# Rocekt_test_stand_input_2_0.net
KiCad netlist of a schematic drawn in EAGLE
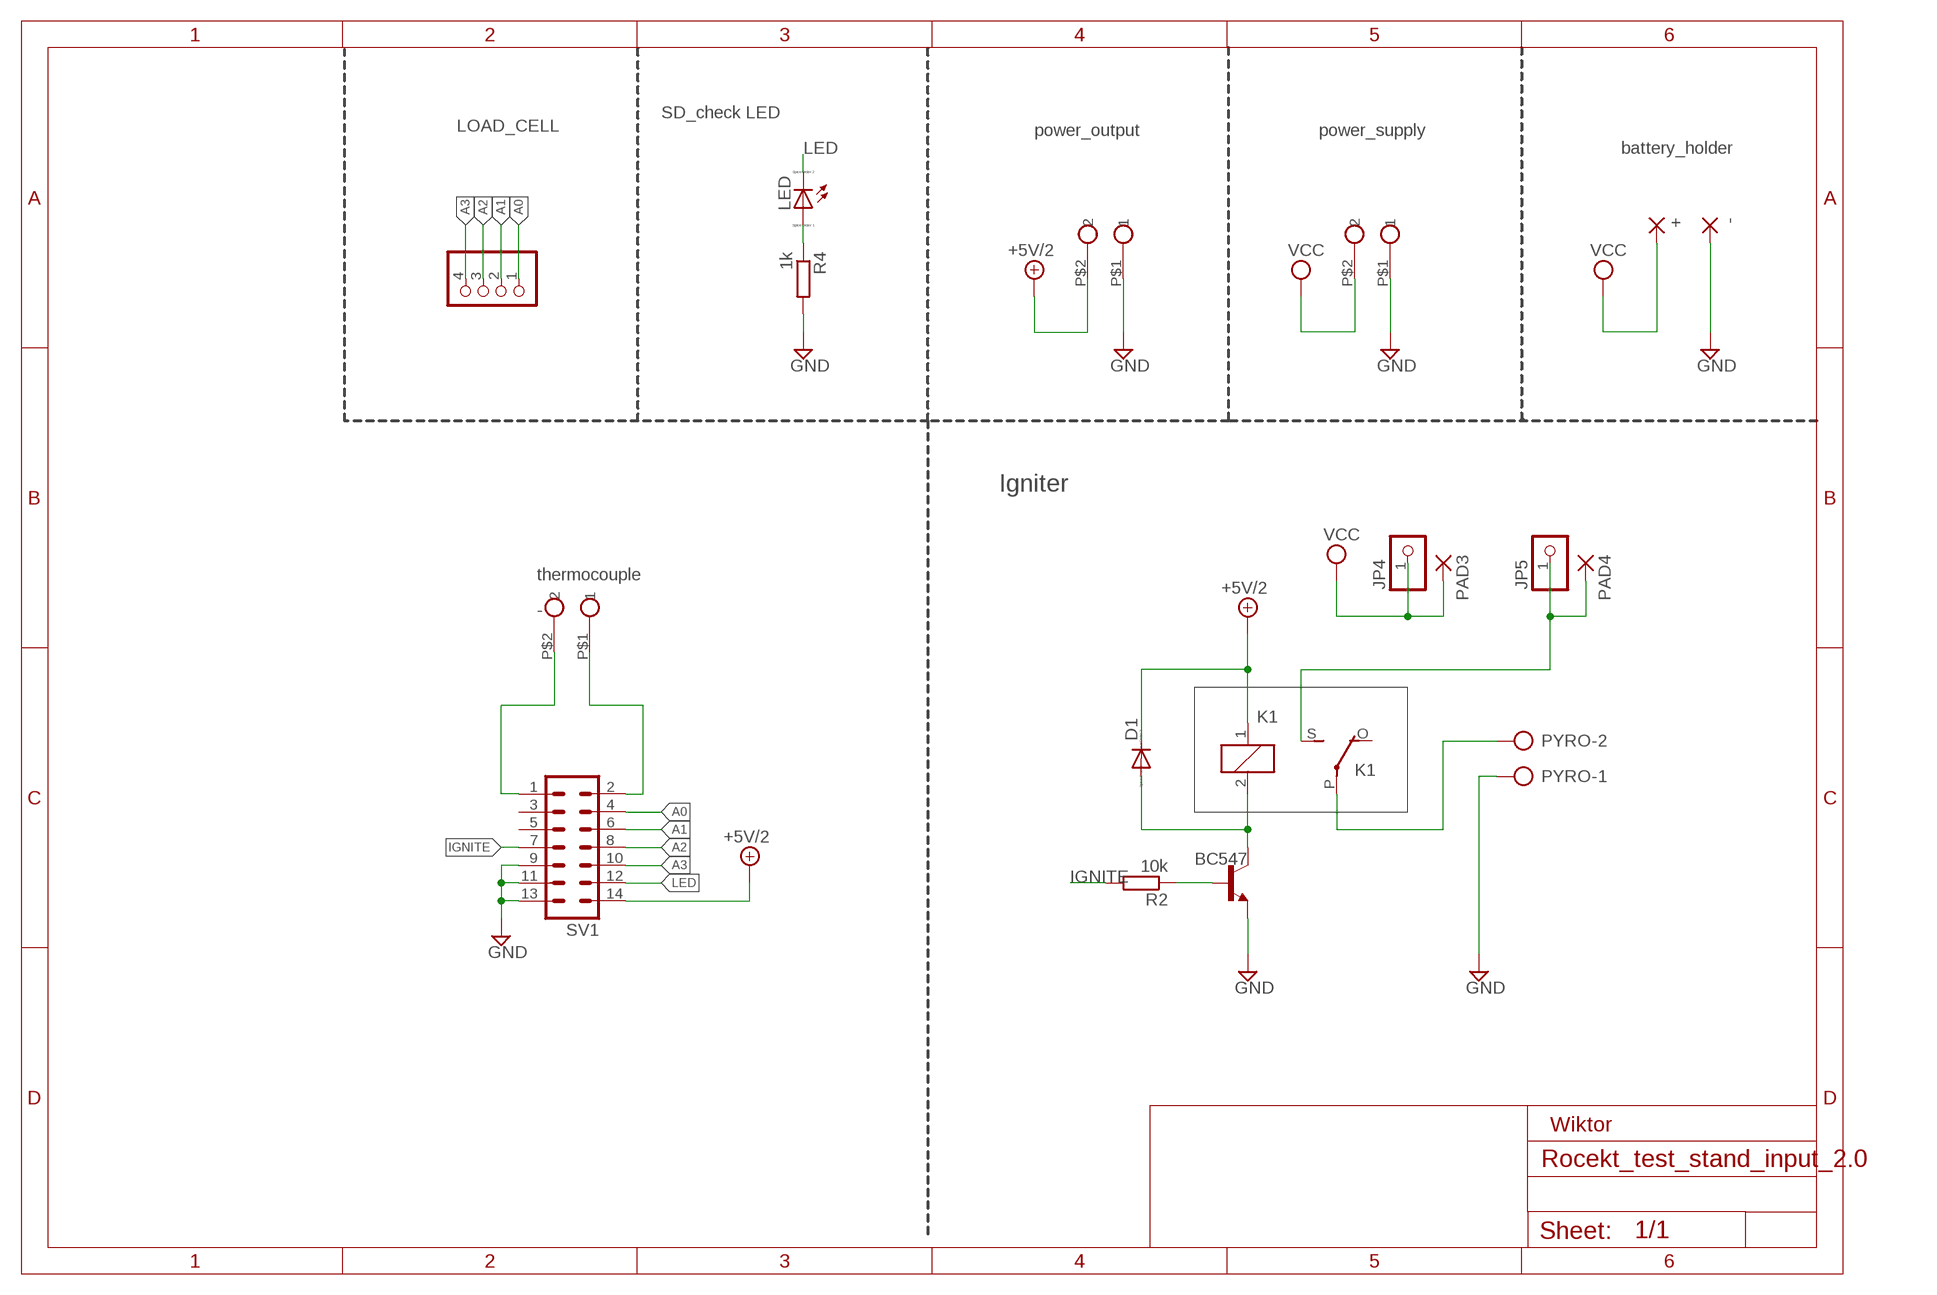
[diagram p0: schematic, sheet 1]

(export (version "E")
  (design (tool "Eeschema 10.0.6"))
  (components
    (comp (ref "+")
      (value "SMD5")
      (footprint "eagle-import:SMD2,54-5,08")
      (libsource (lib "eagle-import") (part "SMD5"))
    )
    (comp (ref "-")
      (value "SMD5")
      (footprint "eagle-import:SMD2,54-5,08")
      (libsource (lib "eagle-import") (part "SMD5"))
    )
    (comp (ref "D1")
      (value "1N4004")
      (footprint "eagle-import:DO41-10")
      (libsource (lib "eagle-import") (part "1N4004"))
    )
    (comp (ref "JP4")
      (value "PINHD-1X1")
      (footprint "eagle-import:1X01")
      (libsource (lib "eagle-import") (part "PINHD-1X1"))
    )
    (comp (ref "JP5")
      (value "PINHD-1X1")
      (footprint "eagle-import:1X01")
      (libsource (lib "eagle-import") (part "PINHD-1X1"))
    )
    (comp (ref "K1")
      (value "G5L")
      (footprint "eagle-import:G5LE")
      (libsource (lib "eagle-import") (part "G5L"))
    )
    (comp (ref "LED")
      (value "LED_ELD260")
      (footprint "eagle-import:LED_LD260")
      (libsource (lib "eagle-import") (part "LED_ELD260"))
    )
    (comp (ref "LOAD_CELL")
      (value "PINHD-1X4")
      (footprint "eagle-import:1X04")
      (libsource (lib "eagle-import") (part "PINHD-1X4"))
    )
    (comp (ref "PAD3")
      (value "SMD2")
      (footprint "eagle-import:SMD1,27-2,54")
      (libsource (lib "eagle-import") (part "SMD2"))
    )
    (comp (ref "PAD4")
      (value "SMD2")
      (footprint "eagle-import:SMD1,27-2,54")
      (libsource (lib "eagle-import") (part "SMD2"))
    )
    (comp (ref "POWER_SUPPLY")
      (value "ARK_8.5MM")
      (footprint "eagle-import:ZLACZESRUBOWE8.5MM")
      (libsource (lib "eagle-import") (part "ARK_8.5MM"))
    )
    (comp (ref "POWER_SUPPLY1")
      (value "ARK_8.5MM")
      (footprint "eagle-import:ZLACZESRUBOWE8.5MM")
      (libsource (lib "eagle-import") (part "ARK_8.5MM"))
    )
    (comp (ref "PYRO")
      (value "AK500/2")
      (footprint "eagle-import:AK500_2")
      (libsource (lib "eagle-import") (part "AK500/2"))
    )
    (comp (ref "R2")
      (value "10k")
      (footprint "eagle-import:0204_5")
      (libsource (lib "eagle-import") (part "R-EU_0204/5"))
    )
    (comp (ref "R4")
      (value "1k")
      (footprint "eagle-import:0204_5")
      (libsource (lib "eagle-import") (part "R-EU_0204/5"))
    )
    (comp (ref "SV1")
      (value "ML14")
      (footprint "eagle-import:ML14")
      (libsource (lib "eagle-import") (part "ML14"))
    )
    (comp (ref "T1")
      (value "BC547")
      (footprint "eagle-import:TO92")
      (libsource (lib "eagle-import") (part "BC547"))
    )
    (comp (ref "U$1")
      (value "ARK_8.5MM")
      (footprint "eagle-import:ZLACZESRUBOWE8.5MM")
      (libsource (lib "eagle-import") (part "ARK_8.5MM"))
    )
  )
  (nets
    (net (code "1") (name "+5V{slash}2") (class "Default")
      (node (ref "D1") (pin "C") (pinfunction "C_C") (pintype "passive"))
      (node (ref "K1") (pin "1") (pinfunction "1_1") (pintype "passive"))
      (node (ref "POWER_SUPPLY1") (pin "P$2") (pinfunction "2_P$2") (pintype "bidirectional"))
      (node (ref "SV1") (pin "14") (pinfunction "14_14") (pintype "passive"))
    )
    (net (code "2") (name "/-") (class "Default")
      (node (ref "SV1") (pin "1") (pinfunction "1_1") (pintype "passive"))
      (node (ref "U$1") (pin "P$2") (pinfunction "2_P$2") (pintype "bidirectional"))
    )
    (net (code "3") (name "A0") (class "Default")
      (node (ref "LOAD_CELL") (pin "1") (pinfunction "1_1") (pintype "passive"))
      (node (ref "SV1") (pin "4") (pinfunction "4_4") (pintype "passive"))
    )
    (net (code "4") (name "A1") (class "Default")
      (node (ref "LOAD_CELL") (pin "2") (pinfunction "2_2") (pintype "passive"))
      (node (ref "SV1") (pin "6") (pinfunction "6_6") (pintype "passive"))
    )
    (net (code "5") (name "A2") (class "Default")
      (node (ref "LOAD_CELL") (pin "3") (pinfunction "3_3") (pintype "passive"))
      (node (ref "SV1") (pin "8") (pinfunction "8_8") (pintype "passive"))
    )
    (net (code "6") (name "A3") (class "Default")
      (node (ref "LOAD_CELL") (pin "4") (pinfunction "4_4") (pintype "passive"))
      (node (ref "SV1") (pin "10") (pinfunction "10_10") (pintype "passive"))
    )
    (net (code "7") (name "GND") (class "Default")
      (node (ref "-") (pin "1") (pinfunction "P_1") (pintype "passive"))
      (node (ref "POWER_SUPPLY") (pin "P$1") (pinfunction "1_P$1") (pintype "bidirectional"))
      (node (ref "POWER_SUPPLY1") (pin "P$1") (pinfunction "1_P$1") (pintype "bidirectional"))
      (node (ref "PYRO") (pin "1") (pinfunction "KL_1") (pintype "passive"))
      (node (ref "R4") (pin "2") (pinfunction "2_2") (pintype "passive"))
      (node (ref "SV1") (pin "11") (pinfunction "11_11") (pintype "passive"))
      (node (ref "SV1") (pin "13") (pinfunction "13_13") (pintype "passive"))
      (node (ref "SV1") (pin "9") (pinfunction "9_9") (pintype "passive"))
      (node (ref "T1") (pin "1") (pinfunction "E_1") (pintype "passive"))
    )
    (net (code "8") (name "IGNITE") (class "Default")
      (node (ref "R2") (pin "2") (pinfunction "2_2") (pintype "passive"))
      (node (ref "SV1") (pin "7") (pinfunction "7_7") (pintype "passive"))
    )
    (net (code "9") (name "LED") (class "Default")
      (node (ref "LED") (pin "K") (pinfunction "C_K") (pintype "passive"))
      (node (ref "SV1") (pin "12") (pinfunction "12_12") (pintype "passive"))
    )
    (net (code "10") (name "Net-(LED-PadA)") (class "Default")
      (node (ref "LED") (pin "A") (pinfunction "A_A") (pintype "passive"))
      (node (ref "R4") (pin "1") (pinfunction "1_1") (pintype "passive"))
    )
    (net (code "11") (name "Net-(PAD4-P)") (class "Default")
      (node (ref "JP5") (pin "1") (pinfunction "1_1") (pintype "passive"))
      (node (ref "K1") (pin "S") (pinfunction "S_S") (pintype "passive"))
      (node (ref "PAD4") (pin "1") (pinfunction "P_1") (pintype "passive"))
    )
    (net (code "12") (name "Net-(PYROB-KL)") (class "Default")
      (node (ref "K1") (pin "P") (pinfunction "P_P") (pintype "passive"))
      (node (ref "PYRO") (pin "2") (pinfunction "KL_2") (pintype "passive"))
    )
    (net (code "13") (name "Net-(T1-B)") (class "Default")
      (node (ref "R2") (pin "1") (pinfunction "1_1") (pintype "passive"))
      (node (ref "T1") (pin "2") (pinfunction "B_2") (pintype "passive"))
    )
    (net (code "14") (name "Net-(T1-C)") (class "Default")
      (node (ref "D1") (pin "A") (pinfunction "A_A") (pintype "passive"))
      (node (ref "K1") (pin "2") (pinfunction "2_2") (pintype "passive"))
      (node (ref "T1") (pin "3") (pinfunction "C_3") (pintype "passive"))
    )
    (net (code "15") (name "Net-(U$1-1)") (class "Default")
      (node (ref "SV1") (pin "2") (pinfunction "2_2") (pintype "passive"))
      (node (ref "U$1") (pin "P$1") (pinfunction "1_P$1") (pintype "bidirectional"))
    )
    (net (code "16") (name "VCC") (class "Default")
      (node (ref "+") (pin "1") (pinfunction "P_1") (pintype "passive"))
      (node (ref "JP4") (pin "1") (pinfunction "1_1") (pintype "passive"))
      (node (ref "PAD3") (pin "1") (pinfunction "P_1") (pintype "passive"))
      (node (ref "POWER_SUPPLY") (pin "P$2") (pinfunction "2_P$2") (pintype "bidirectional"))
    )
    (net (code "17") (name "unconnected-(K1-PadO)") (class "Default")
      (node (ref "K1") (pin "O") (pinfunction "O_O") (pintype "passive"))
    )
    (net (code "18") (name "unconnected-(SV1-Pad3)") (class "Default")
      (node (ref "SV1") (pin "3") (pinfunction "3_3") (pintype "passive"))
    )
    (net (code "19") (name "unconnected-(SV1-Pad5)") (class "Default")
      (node (ref "SV1") (pin "5") (pinfunction "5_5") (pintype "passive"))
    )
  )
)
